# sdram_xxsd_1_0.net
KiCad netlist of a schematic drawn in EAGLE
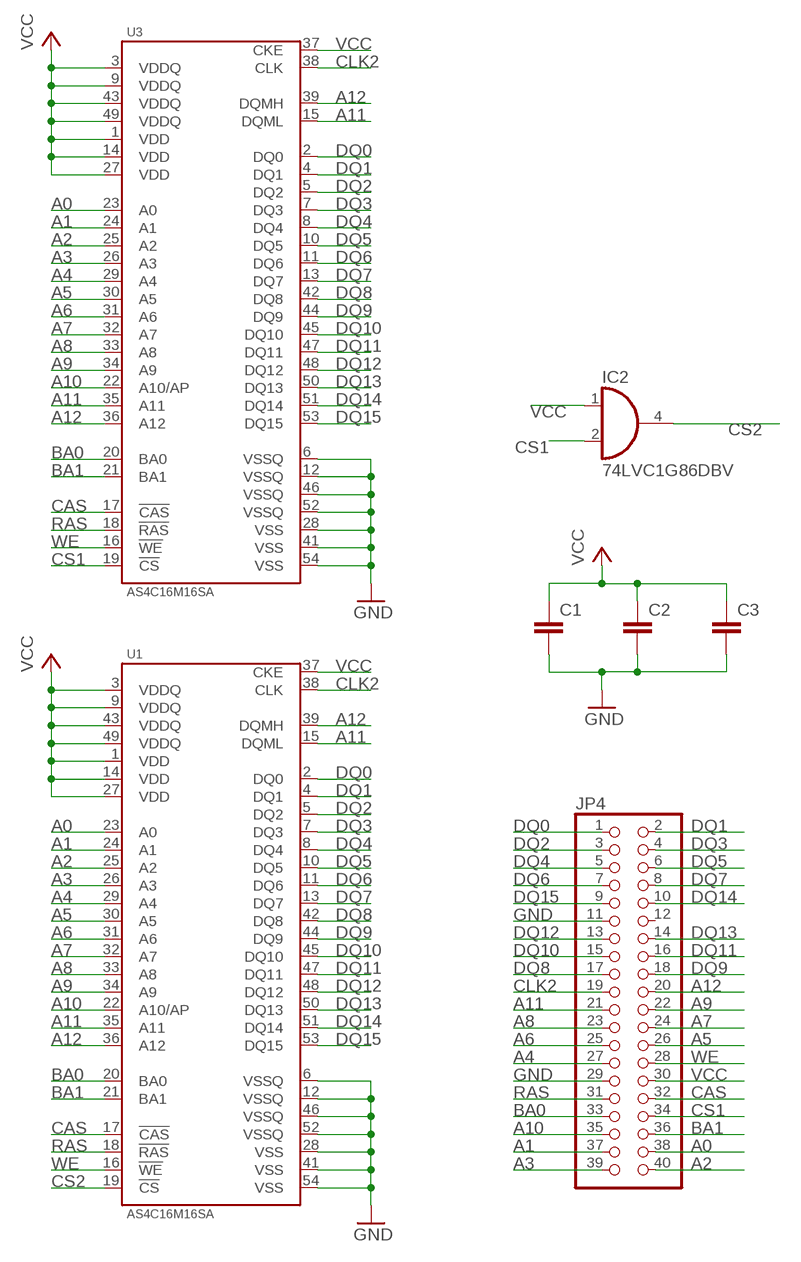
[diagram p0: schematic, sheet 1]

(export (version "E")
  (design (tool "Eeschema 10.0.6"))
  (components
    (comp (ref "C1")
      (value "C-EUC0805K")
      (footprint "eagle-import:C0805K")
      (libsource (lib "eagle-import") (part "C-EUC0805K"))
    )
    (comp (ref "C2")
      (value "C-EUC0805K")
      (footprint "eagle-import:C0805K")
      (libsource (lib "eagle-import") (part "C-EUC0805K"))
    )
    (comp (ref "C3")
      (value "C-EUC0805K")
      (footprint "eagle-import:C0805K")
      (libsource (lib "eagle-import") (part "C-EUC0805K"))
    )
    (comp (ref "IC2")
      (value "74LVC1G86DBV")
      (footprint "eagle-import:SOT23-5")
      (libsource (lib "eagle-import") (part "741G08DBVLVC"))
    )
    (comp (ref "JP4")
      (value "PINHD-2X20_2.54-SMD")
      (footprint "eagle-import:2X20SMD")
      (libsource (lib "eagle-import") (part "PINHD-2X20_2.54-SMD"))
    )
    (comp (ref "U1")
      (value "AS4C16M16SA")
      (footprint "eagle-import:TSOPII-54")
      (libsource (lib "eagle-import") (part "AS4C16M16SA"))
    )
    (comp (ref "U3")
      (value "AS4C16M16SA")
      (footprint "eagle-import:TSOPII-54")
      (libsource (lib "eagle-import") (part "AS4C16M16SA"))
    )
  )
  (nets
    (net (code "1") (name "/A0") (class "Default")
      (node (ref "JP4") (pin "38") (pinfunction "38_38") (pintype "passive"))
      (node (ref "U1") (pin "23") (pinfunction "A0_23") (pintype "bidirectional"))
      (node (ref "U3") (pin "23") (pinfunction "A0_23") (pintype "bidirectional"))
    )
    (net (code "2") (name "/A1") (class "Default")
      (node (ref "JP4") (pin "37") (pinfunction "37_37") (pintype "passive"))
      (node (ref "U1") (pin "24") (pinfunction "A1_24") (pintype "bidirectional"))
      (node (ref "U3") (pin "24") (pinfunction "A1_24") (pintype "bidirectional"))
    )
    (net (code "3") (name "/A2") (class "Default")
      (node (ref "JP4") (pin "40") (pinfunction "40_40") (pintype "passive"))
      (node (ref "U1") (pin "25") (pinfunction "A2_25") (pintype "bidirectional"))
      (node (ref "U3") (pin "25") (pinfunction "A2_25") (pintype "bidirectional"))
    )
    (net (code "4") (name "/A3") (class "Default")
      (node (ref "JP4") (pin "39") (pinfunction "39_39") (pintype "passive"))
      (node (ref "U1") (pin "26") (pinfunction "A3_26") (pintype "bidirectional"))
      (node (ref "U3") (pin "26") (pinfunction "A3_26") (pintype "bidirectional"))
    )
    (net (code "5") (name "/A4") (class "Default")
      (node (ref "JP4") (pin "27") (pinfunction "27_27") (pintype "passive"))
      (node (ref "U1") (pin "29") (pinfunction "A4_29") (pintype "bidirectional"))
      (node (ref "U3") (pin "29") (pinfunction "A4_29") (pintype "bidirectional"))
    )
    (net (code "6") (name "/A5") (class "Default")
      (node (ref "JP4") (pin "26") (pinfunction "26_26") (pintype "passive"))
      (node (ref "U1") (pin "30") (pinfunction "A5_30") (pintype "bidirectional"))
      (node (ref "U3") (pin "30") (pinfunction "A5_30") (pintype "bidirectional"))
    )
    (net (code "7") (name "/A6") (class "Default")
      (node (ref "JP4") (pin "25") (pinfunction "25_25") (pintype "passive"))
      (node (ref "U1") (pin "31") (pinfunction "A6_31") (pintype "bidirectional"))
      (node (ref "U3") (pin "31") (pinfunction "A6_31") (pintype "bidirectional"))
    )
    (net (code "8") (name "/A7") (class "Default")
      (node (ref "JP4") (pin "24") (pinfunction "24_24") (pintype "passive"))
      (node (ref "U1") (pin "32") (pinfunction "A7_32") (pintype "bidirectional"))
      (node (ref "U3") (pin "32") (pinfunction "A7_32") (pintype "bidirectional"))
    )
    (net (code "9") (name "/A8") (class "Default")
      (node (ref "JP4") (pin "23") (pinfunction "23_23") (pintype "passive"))
      (node (ref "U1") (pin "33") (pinfunction "A8_33") (pintype "bidirectional"))
      (node (ref "U3") (pin "33") (pinfunction "A8_33") (pintype "bidirectional"))
    )
    (net (code "10") (name "/A9") (class "Default")
      (node (ref "JP4") (pin "22") (pinfunction "22_22") (pintype "passive"))
      (node (ref "U1") (pin "34") (pinfunction "A9_34") (pintype "bidirectional"))
      (node (ref "U3") (pin "34") (pinfunction "A9_34") (pintype "bidirectional"))
    )
    (net (code "11") (name "/A10") (class "Default")
      (node (ref "JP4") (pin "35") (pinfunction "35_35") (pintype "passive"))
      (node (ref "U1") (pin "22") (pinfunction "A10/AP_22") (pintype "bidirectional"))
      (node (ref "U3") (pin "22") (pinfunction "A10/AP_22") (pintype "bidirectional"))
    )
    (net (code "12") (name "/A11") (class "Default")
      (node (ref "JP4") (pin "21") (pinfunction "21_21") (pintype "passive"))
      (node (ref "U1") (pin "15") (pinfunction "DQML_15") (pintype "bidirectional"))
      (node (ref "U1") (pin "35") (pinfunction "A11_35") (pintype "bidirectional"))
      (node (ref "U3") (pin "15") (pinfunction "DQML_15") (pintype "bidirectional"))
      (node (ref "U3") (pin "35") (pinfunction "A11_35") (pintype "bidirectional"))
    )
    (net (code "13") (name "/A12") (class "Default")
      (node (ref "JP4") (pin "20") (pinfunction "20_20") (pintype "passive"))
      (node (ref "U1") (pin "36") (pinfunction "A12_36") (pintype "bidirectional"))
      (node (ref "U1") (pin "39") (pinfunction "DQMH_39") (pintype "bidirectional"))
      (node (ref "U3") (pin "36") (pinfunction "A12_36") (pintype "bidirectional"))
      (node (ref "U3") (pin "39") (pinfunction "DQMH_39") (pintype "bidirectional"))
    )
    (net (code "14") (name "/BA0") (class "Default")
      (node (ref "JP4") (pin "33") (pinfunction "33_33") (pintype "passive"))
      (node (ref "U1") (pin "20") (pinfunction "BA0_20") (pintype "bidirectional"))
      (node (ref "U3") (pin "20") (pinfunction "BA0_20") (pintype "bidirectional"))
    )
    (net (code "15") (name "/BA1") (class "Default")
      (node (ref "JP4") (pin "36") (pinfunction "36_36") (pintype "passive"))
      (node (ref "U1") (pin "21") (pinfunction "BA1_21") (pintype "bidirectional"))
      (node (ref "U3") (pin "21") (pinfunction "BA1_21") (pintype "bidirectional"))
    )
    (net (code "16") (name "/CAS") (class "Default")
      (node (ref "JP4") (pin "32") (pinfunction "32_32") (pintype "passive"))
      (node (ref "U1") (pin "17") (pinfunction "~{CAS}_17") (pintype "bidirectional"))
      (node (ref "U3") (pin "17") (pinfunction "~{CAS}_17") (pintype "bidirectional"))
    )
    (net (code "17") (name "/CLK2") (class "Default")
      (node (ref "JP4") (pin "19") (pinfunction "19_19") (pintype "passive"))
      (node (ref "U1") (pin "38") (pinfunction "CLK_38") (pintype "bidirectional"))
      (node (ref "U3") (pin "38") (pinfunction "CLK_38") (pintype "bidirectional"))
    )
    (net (code "18") (name "/CS1") (class "Default")
      (node (ref "IC2") (pin "2") (pinfunction "I1_2") (pintype "input"))
      (node (ref "JP4") (pin "34") (pinfunction "34_34") (pintype "passive"))
      (node (ref "U3") (pin "19") (pinfunction "~{CS}_19") (pintype "bidirectional"))
    )
    (net (code "19") (name "/CS2") (class "Default")
      (node (ref "IC2") (pin "4") (pinfunction "O_4") (pintype "output"))
      (node (ref "U1") (pin "19") (pinfunction "~{CS}_19") (pintype "bidirectional"))
    )
    (net (code "20") (name "/DQ0") (class "Default")
      (node (ref "JP4") (pin "1") (pinfunction "1_1") (pintype "passive"))
      (node (ref "U1") (pin "2") (pinfunction "DQ0_2") (pintype "bidirectional"))
      (node (ref "U3") (pin "2") (pinfunction "DQ0_2") (pintype "bidirectional"))
    )
    (net (code "21") (name "/DQ1") (class "Default")
      (node (ref "JP4") (pin "2") (pinfunction "2_2") (pintype "passive"))
      (node (ref "U1") (pin "4") (pinfunction "DQ1_4") (pintype "bidirectional"))
      (node (ref "U3") (pin "4") (pinfunction "DQ1_4") (pintype "bidirectional"))
    )
    (net (code "22") (name "/DQ2") (class "Default")
      (node (ref "JP4") (pin "3") (pinfunction "3_3") (pintype "passive"))
      (node (ref "U1") (pin "5") (pinfunction "DQ2_5") (pintype "bidirectional"))
      (node (ref "U3") (pin "5") (pinfunction "DQ2_5") (pintype "bidirectional"))
    )
    (net (code "23") (name "/DQ3") (class "Default")
      (node (ref "JP4") (pin "4") (pinfunction "4_4") (pintype "passive"))
      (node (ref "U1") (pin "7") (pinfunction "DQ3_7") (pintype "bidirectional"))
      (node (ref "U3") (pin "7") (pinfunction "DQ3_7") (pintype "bidirectional"))
    )
    (net (code "24") (name "/DQ4") (class "Default")
      (node (ref "JP4") (pin "5") (pinfunction "5_5") (pintype "passive"))
      (node (ref "U1") (pin "8") (pinfunction "DQ4_8") (pintype "bidirectional"))
      (node (ref "U3") (pin "8") (pinfunction "DQ4_8") (pintype "bidirectional"))
    )
    (net (code "25") (name "/DQ5") (class "Default")
      (node (ref "JP4") (pin "6") (pinfunction "6_6") (pintype "passive"))
      (node (ref "U1") (pin "10") (pinfunction "DQ5_10") (pintype "bidirectional"))
      (node (ref "U3") (pin "10") (pinfunction "DQ5_10") (pintype "bidirectional"))
    )
    (net (code "26") (name "/DQ6") (class "Default")
      (node (ref "JP4") (pin "7") (pinfunction "7_7") (pintype "passive"))
      (node (ref "U1") (pin "11") (pinfunction "DQ6_11") (pintype "bidirectional"))
      (node (ref "U3") (pin "11") (pinfunction "DQ6_11") (pintype "bidirectional"))
    )
    (net (code "27") (name "/DQ7") (class "Default")
      (node (ref "JP4") (pin "8") (pinfunction "8_8") (pintype "passive"))
      (node (ref "U1") (pin "13") (pinfunction "DQ7_13") (pintype "bidirectional"))
      (node (ref "U3") (pin "13") (pinfunction "DQ7_13") (pintype "bidirectional"))
    )
    (net (code "28") (name "/DQ8") (class "Default")
      (node (ref "JP4") (pin "17") (pinfunction "17_17") (pintype "passive"))
      (node (ref "U1") (pin "42") (pinfunction "DQ8_42") (pintype "bidirectional"))
      (node (ref "U3") (pin "42") (pinfunction "DQ8_42") (pintype "bidirectional"))
    )
    (net (code "29") (name "/DQ9") (class "Default")
      (node (ref "JP4") (pin "18") (pinfunction "18_18") (pintype "passive"))
      (node (ref "U1") (pin "44") (pinfunction "DQ9_44") (pintype "bidirectional"))
      (node (ref "U3") (pin "44") (pinfunction "DQ9_44") (pintype "bidirectional"))
    )
    (net (code "30") (name "/DQ10") (class "Default")
      (node (ref "JP4") (pin "15") (pinfunction "15_15") (pintype "passive"))
      (node (ref "U1") (pin "45") (pinfunction "DQ10_45") (pintype "bidirectional"))
      (node (ref "U3") (pin "45") (pinfunction "DQ10_45") (pintype "bidirectional"))
    )
    (net (code "31") (name "/DQ11") (class "Default")
      (node (ref "JP4") (pin "16") (pinfunction "16_16") (pintype "passive"))
      (node (ref "U1") (pin "47") (pinfunction "DQ11_47") (pintype "bidirectional"))
      (node (ref "U3") (pin "47") (pinfunction "DQ11_47") (pintype "bidirectional"))
    )
    (net (code "32") (name "/DQ12") (class "Default")
      (node (ref "JP4") (pin "13") (pinfunction "13_13") (pintype "passive"))
      (node (ref "U1") (pin "48") (pinfunction "DQ12_48") (pintype "bidirectional"))
      (node (ref "U3") (pin "48") (pinfunction "DQ12_48") (pintype "bidirectional"))
    )
    (net (code "33") (name "/DQ13") (class "Default")
      (node (ref "JP4") (pin "14") (pinfunction "14_14") (pintype "passive"))
      (node (ref "U1") (pin "50") (pinfunction "DQ13_50") (pintype "bidirectional"))
      (node (ref "U3") (pin "50") (pinfunction "DQ13_50") (pintype "bidirectional"))
    )
    (net (code "34") (name "/DQ14") (class "Default")
      (node (ref "JP4") (pin "10") (pinfunction "10_10") (pintype "passive"))
      (node (ref "U1") (pin "51") (pinfunction "DQ14_51") (pintype "bidirectional"))
      (node (ref "U3") (pin "51") (pinfunction "DQ14_51") (pintype "bidirectional"))
    )
    (net (code "35") (name "/DQ15") (class "Default")
      (node (ref "JP4") (pin "9") (pinfunction "9_9") (pintype "passive"))
      (node (ref "U1") (pin "53") (pinfunction "DQ15_53") (pintype "bidirectional"))
      (node (ref "U3") (pin "53") (pinfunction "DQ15_53") (pintype "bidirectional"))
    )
    (net (code "36") (name "/RAS") (class "Default")
      (node (ref "JP4") (pin "31") (pinfunction "31_31") (pintype "passive"))
      (node (ref "U1") (pin "18") (pinfunction "~{RAS}_18") (pintype "bidirectional"))
      (node (ref "U3") (pin "18") (pinfunction "~{RAS}_18") (pintype "bidirectional"))
    )
    (net (code "37") (name "/WE") (class "Default")
      (node (ref "JP4") (pin "28") (pinfunction "28_28") (pintype "passive"))
      (node (ref "U1") (pin "16") (pinfunction "~{WE}_16") (pintype "bidirectional"))
      (node (ref "U3") (pin "16") (pinfunction "~{WE}_16") (pintype "bidirectional"))
    )
    (net (code "38") (name "GND") (class "Default")
      (node (ref "C1") (pin "2") (pinfunction "2_2") (pintype "passive"))
      (node (ref "C2") (pin "2") (pinfunction "2_2") (pintype "passive"))
      (node (ref "C3") (pin "2") (pinfunction "2_2") (pintype "passive"))
      (node (ref "JP4") (pin "11") (pinfunction "11_11") (pintype "passive"))
      (node (ref "JP4") (pin "29") (pinfunction "29_29") (pintype "passive"))
      (node (ref "U1") (pin "12") (pinfunction "VSSQ_12") (pintype "bidirectional"))
      (node (ref "U1") (pin "28") (pinfunction "VSS_28") (pintype "bidirectional"))
      (node (ref "U1") (pin "41") (pinfunction "VSS_41") (pintype "bidirectional"))
      (node (ref "U1") (pin "46") (pinfunction "VSSQ_46") (pintype "bidirectional"))
      (node (ref "U1") (pin "52") (pinfunction "VSSQ_52") (pintype "bidirectional"))
      (node (ref "U1") (pin "54") (pinfunction "VSS_54") (pintype "bidirectional"))
      (node (ref "U1") (pin "6") (pinfunction "VSSQ_6") (pintype "bidirectional"))
      (node (ref "U3") (pin "12") (pinfunction "VSSQ_12") (pintype "bidirectional"))
      (node (ref "U3") (pin "28") (pinfunction "VSS_28") (pintype "bidirectional"))
      (node (ref "U3") (pin "41") (pinfunction "VSS_41") (pintype "bidirectional"))
      (node (ref "U3") (pin "46") (pinfunction "VSSQ_46") (pintype "bidirectional"))
      (node (ref "U3") (pin "52") (pinfunction "VSSQ_52") (pintype "bidirectional"))
      (node (ref "U3") (pin "54") (pinfunction "VSS_54") (pintype "bidirectional"))
      (node (ref "U3") (pin "6") (pinfunction "VSSQ_6") (pintype "bidirectional"))
    )
    (net (code "39") (name "VCC") (class "Default")
      (node (ref "C1") (pin "1") (pinfunction "1_1") (pintype "passive"))
      (node (ref "C2") (pin "1") (pinfunction "1_1") (pintype "passive"))
      (node (ref "C3") (pin "1") (pinfunction "1_1") (pintype "passive"))
      (node (ref "IC2") (pin "1") (pinfunction "I0_1") (pintype "input"))
      (node (ref "JP4") (pin "30") (pinfunction "30_30") (pintype "passive"))
      (node (ref "U1") (pin "1") (pinfunction "VDD_1") (pintype "bidirectional"))
      (node (ref "U1") (pin "14") (pinfunction "VDD_14") (pintype "bidirectional"))
      (node (ref "U1") (pin "27") (pinfunction "VDD_27") (pintype "bidirectional"))
      (node (ref "U1") (pin "3") (pinfunction "VDDQ_3") (pintype "bidirectional"))
      (node (ref "U1") (pin "37") (pinfunction "CKE_37") (pintype "bidirectional"))
      (node (ref "U1") (pin "43") (pinfunction "VDDQ_43") (pintype "bidirectional"))
      (node (ref "U1") (pin "49") (pinfunction "VDDQ_49") (pintype "bidirectional"))
      (node (ref "U1") (pin "9") (pinfunction "VDDQ_9") (pintype "bidirectional"))
      (node (ref "U3") (pin "1") (pinfunction "VDD_1") (pintype "bidirectional"))
      (node (ref "U3") (pin "14") (pinfunction "VDD_14") (pintype "bidirectional"))
      (node (ref "U3") (pin "27") (pinfunction "VDD_27") (pintype "bidirectional"))
      (node (ref "U3") (pin "3") (pinfunction "VDDQ_3") (pintype "bidirectional"))
      (node (ref "U3") (pin "37") (pinfunction "CKE_37") (pintype "bidirectional"))
      (node (ref "U3") (pin "43") (pinfunction "VDDQ_43") (pintype "bidirectional"))
      (node (ref "U3") (pin "49") (pinfunction "VDDQ_49") (pintype "bidirectional"))
      (node (ref "U3") (pin "9") (pinfunction "VDDQ_9") (pintype "bidirectional"))
    )
    (net (code "40") (name "unconnected-(JP4-Pad12)") (class "Default")
      (node (ref "JP4") (pin "12") (pinfunction "12_12") (pintype "passive"))
    )
  )
)
